# tutorial.net
KiCad netlist of a schematic drawn in EAGLE
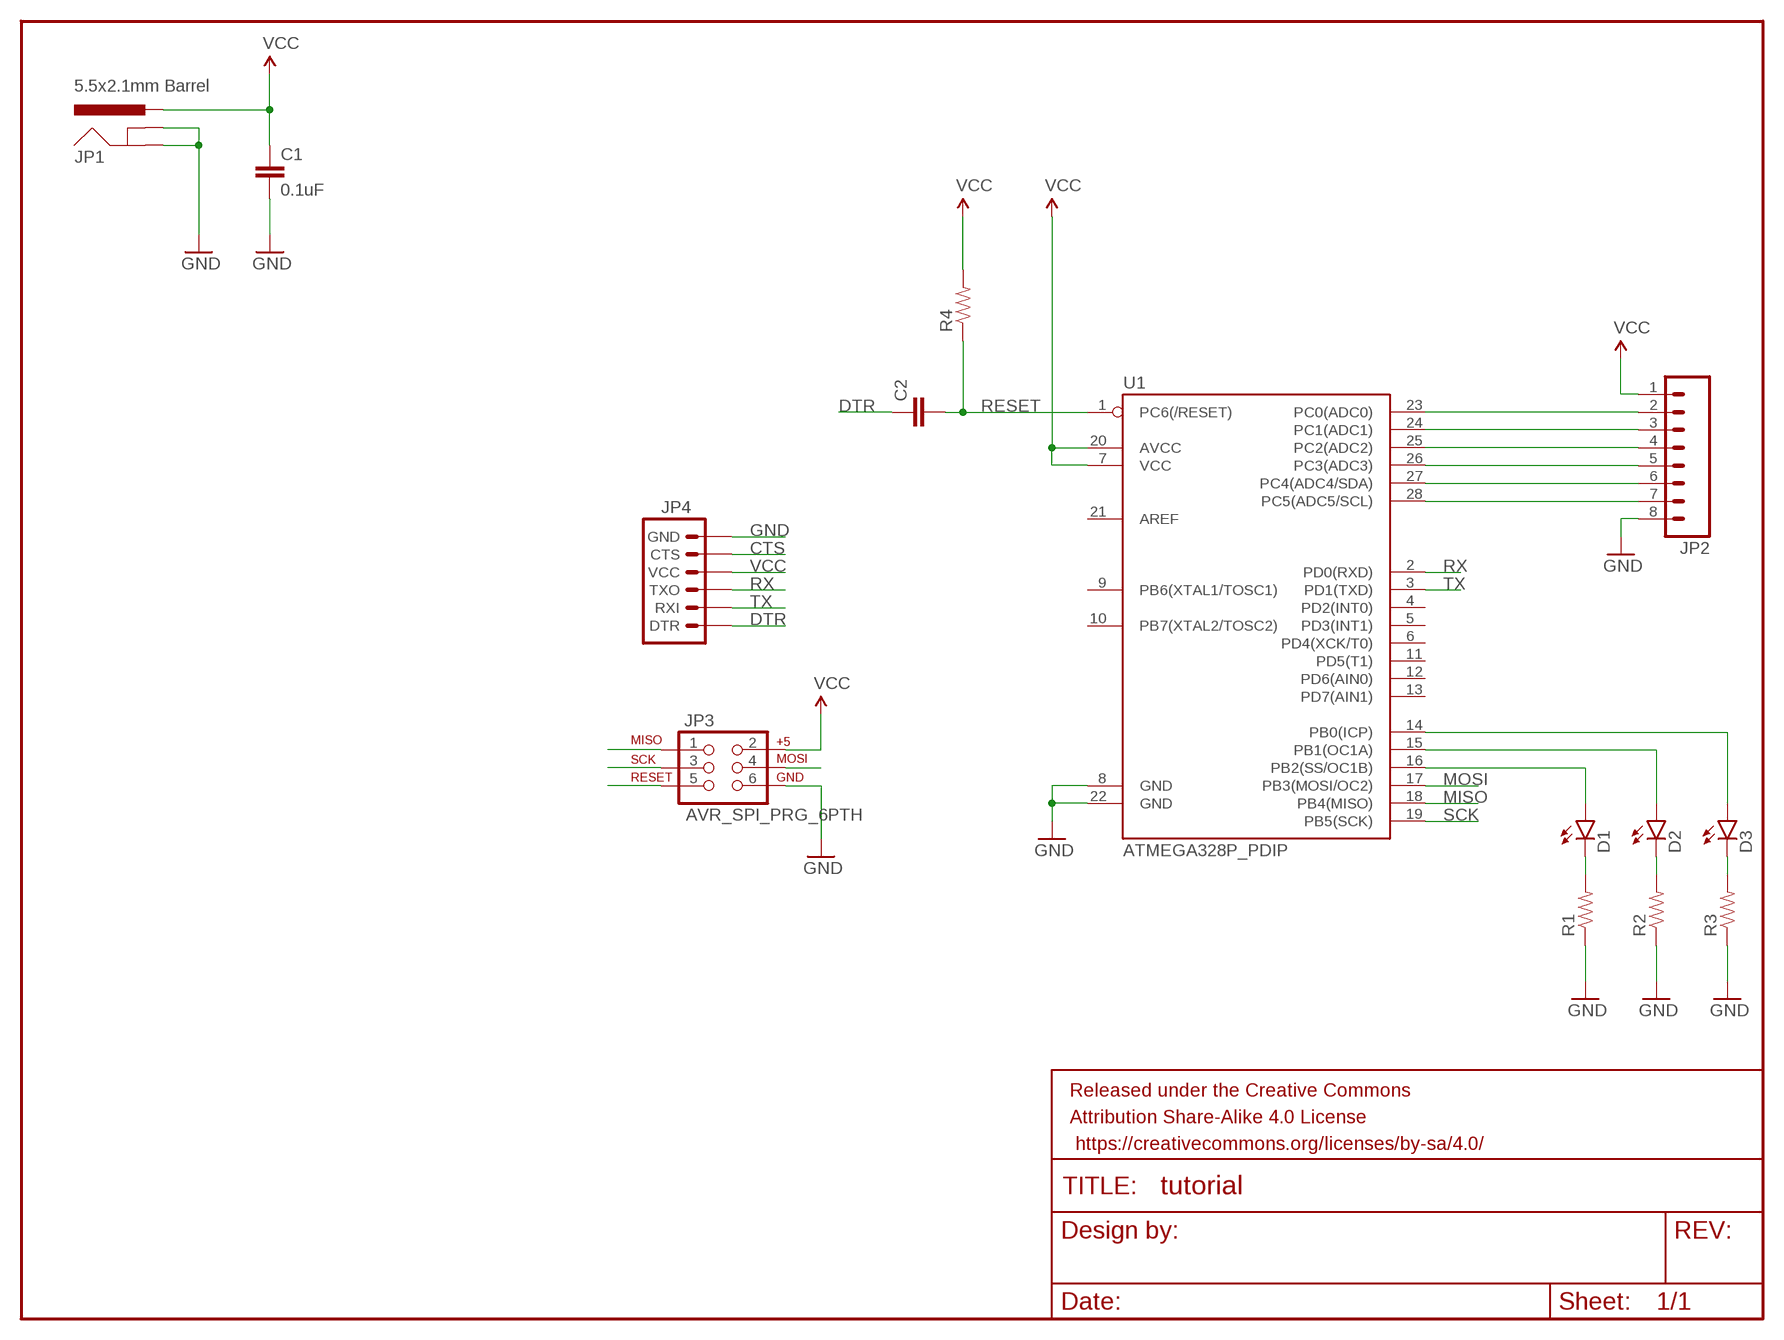
[diagram p0: schematic, sheet 1]

(export (version "E")
  (design (tool "Eeschema 10.0.6"))
  (components
    (comp (ref "C1")
      (value "0.1uF")
      (footprint "eagle-import:CAP-PTH-SMALL")
      (libsource (lib "eagle-import") (part "CAPPTH"))
    )
    (comp (ref "C2")
      (value "CAPPTH")
      (footprint "eagle-import:CAP-PTH-SMALL")
      (libsource (lib "eagle-import") (part "CAPPTH"))
    )
    (comp (ref "D1")
      (value "LED5MM")
      (footprint "eagle-import:LED5MM")
      (libsource (lib "eagle-import") (part "LED5MM"))
    )
    (comp (ref "D2")
      (value "LED5MM")
      (footprint "eagle-import:LED5MM")
      (libsource (lib "eagle-import") (part "LED5MM"))
    )
    (comp (ref "D3")
      (value "LED5MM")
      (footprint "eagle-import:LED5MM")
      (libsource (lib "eagle-import") (part "LED5MM"))
    )
    (comp (ref "FRAME1")
      (value "FRAME-LETTER")
      (footprint "eagle-import:CREATIVE_COMMONS")
      (libsource (lib "eagle-import") (part "FRAME-LETTER"))
    )
    (comp (ref "JP1")
      (value "5.5x2.1mm Barrel")
      (footprint "eagle-import:POWER_JACK_SMD")
      (libsource (lib "eagle-import") (part "POWER_JACKSMD"))
    )
    (comp (ref "JP2")
      (value "M08")
      (footprint "eagle-import:1X08_ROUND")
      (libsource (lib "eagle-import") (part "M08"))
    )
    (comp (ref "JP3")
      (value "AVR_SPI_PRG_6PTH")
      (footprint "eagle-import:2X3")
      (libsource (lib "eagle-import") (part "AVR_SPI_PRG_6PTH"))
    )
    (comp (ref "JP4")
      (value "ARDUINO_SERIAL_PROGRAMPTH")
      (footprint "eagle-import:1X06")
      (libsource (lib "eagle-import") (part "ARDUINO_SERIAL_PROGRAMPTH"))
    )
    (comp (ref "R1")
      (value "RESISTORPTH-1/4W")
      (footprint "eagle-import:AXIAL-0.4")
      (libsource (lib "eagle-import") (part "RESISTORPTH-1/4W"))
    )
    (comp (ref "R2")
      (value "RESISTORPTH-1/4W")
      (footprint "eagle-import:AXIAL-0.4")
      (libsource (lib "eagle-import") (part "RESISTORPTH-1/4W"))
    )
    (comp (ref "R3")
      (value "RESISTORPTH-1/4W")
      (footprint "eagle-import:AXIAL-0.4")
      (libsource (lib "eagle-import") (part "RESISTORPTH-1/4W"))
    )
    (comp (ref "R4")
      (value "RESISTORPTH-1/4W")
      (footprint "eagle-import:AXIAL-0.4")
      (libsource (lib "eagle-import") (part "RESISTORPTH-1/4W"))
    )
    (comp (ref "U1")
      (value "ATMEGA328P_PDIP")
      (footprint "eagle-import:DIL28-3")
      (libsource (lib "eagle-import") (part "ATMEGA328P_PDIP"))
    )
  )
  (nets
    (net (code "1") (name "/CTS") (class "Default")
      (node (ref "JP4") (pin "5") (pinfunction "CTS_5") (pintype "passive"))
    )
    (net (code "2") (name "/DTR") (class "Default")
      (node (ref "C2") (pin "1") (pinfunction "1_1") (pintype "passive"))
      (node (ref "JP4") (pin "1") (pinfunction "DTR_1") (pintype "passive"))
    )
    (net (code "3") (name "/MISO") (class "Default")
      (node (ref "JP3") (pin "1") (pinfunction "1_1") (pintype "passive"))
      (node (ref "U1") (pin "18") (pinfunction "PB4(MISO)_18") (pintype "bidirectional"))
    )
    (net (code "4") (name "/MOSI") (class "Default")
      (node (ref "JP3") (pin "4") (pinfunction "4_4") (pintype "passive"))
      (node (ref "U1") (pin "17") (pinfunction "PB3(MOSI/OC2)_17") (pintype "bidirectional"))
    )
    (net (code "5") (name "/RESET") (class "Default")
      (node (ref "C2") (pin "2") (pinfunction "2_2") (pintype "passive"))
      (node (ref "JP3") (pin "5") (pinfunction "5_5") (pintype "passive"))
      (node (ref "R4") (pin "P$1") (pinfunction "1_P$1") (pintype "passive"))
      (node (ref "U1") (pin "1") (pinfunction "PC6(/RESET)_1") (pintype "bidirectional"))
    )
    (net (code "6") (name "/RX") (class "Default")
      (node (ref "JP4") (pin "3") (pinfunction "TXO_3") (pintype "passive"))
      (node (ref "U1") (pin "2") (pinfunction "PD0(RXD)_2") (pintype "bidirectional"))
    )
    (net (code "7") (name "/SCK") (class "Default")
      (node (ref "JP3") (pin "3") (pinfunction "3_3") (pintype "passive"))
      (node (ref "U1") (pin "19") (pinfunction "PB5(SCK)_19") (pintype "bidirectional"))
    )
    (net (code "8") (name "/TX") (class "Default")
      (node (ref "JP4") (pin "2") (pinfunction "RXI_2") (pintype "passive"))
      (node (ref "U1") (pin "3") (pinfunction "PD1(TXD)_3") (pintype "bidirectional"))
    )
    (net (code "9") (name "GND") (class "Default")
      (node (ref "C1") (pin "2") (pinfunction "2_2") (pintype "passive"))
      (node (ref "JP1") (pin "GND") (pinfunction "GNDBREAK_GND") (pintype "bidirectional"))
      (node (ref "JP1") (pin "P$4") (pinfunction "GND_P$4") (pintype "bidirectional"))
      (node (ref "JP2") (pin "8") (pinfunction "8_8") (pintype "passive"))
      (node (ref "JP3") (pin "6") (pinfunction "6_6") (pintype "passive"))
      (node (ref "JP4") (pin "6") (pinfunction "GND_6") (pintype "passive"))
      (node (ref "R1") (pin "P$1") (pinfunction "1_P$1") (pintype "passive"))
      (node (ref "R2") (pin "P$1") (pinfunction "1_P$1") (pintype "passive"))
      (node (ref "R3") (pin "P$1") (pinfunction "1_P$1") (pintype "passive"))
      (node (ref "U1") (pin "22") (pinfunction "GND_22") (pintype "bidirectional"))
      (node (ref "U1") (pin "8") (pinfunction "GND_8") (pintype "bidirectional"))
    )
    (net (code "10") (name "Net-(D1-C)") (class "Default")
      (node (ref "D1") (pin "K") (pinfunction "C_K") (pintype "passive"))
      (node (ref "R1") (pin "P$2") (pinfunction "2_P$2") (pintype "passive"))
    )
    (net (code "11") (name "Net-(D2-C)") (class "Default")
      (node (ref "D2") (pin "K") (pinfunction "C_K") (pintype "passive"))
      (node (ref "R2") (pin "P$2") (pinfunction "2_P$2") (pintype "passive"))
    )
    (net (code "12") (name "Net-(D3-C)") (class "Default")
      (node (ref "D3") (pin "K") (pinfunction "C_K") (pintype "passive"))
      (node (ref "R3") (pin "P$2") (pinfunction "2_P$2") (pintype "passive"))
    )
    (net (code "13") (name "Net-(U1-PB0(ICP))") (class "Default")
      (node (ref "D3") (pin "A") (pinfunction "A_A") (pintype "passive"))
      (node (ref "U1") (pin "14") (pinfunction "PB0(ICP)_14") (pintype "bidirectional"))
    )
    (net (code "14") (name "Net-(U1-PB1(OC1A))") (class "Default")
      (node (ref "D2") (pin "A") (pinfunction "A_A") (pintype "passive"))
      (node (ref "U1") (pin "15") (pinfunction "PB1(OC1A)_15") (pintype "bidirectional"))
    )
    (net (code "15") (name "Net-(U1-PB2(SS{slash}OC1B))") (class "Default")
      (node (ref "D1") (pin "A") (pinfunction "A_A") (pintype "passive"))
      (node (ref "U1") (pin "16") (pinfunction "PB2(SS/OC1B)_16") (pintype "bidirectional"))
    )
    (net (code "16") (name "Net-(U1-PC0(ADC0))") (class "Default")
      (node (ref "JP2") (pin "2") (pinfunction "2_2") (pintype "passive"))
      (node (ref "U1") (pin "23") (pinfunction "PC0(ADC0)_23") (pintype "bidirectional"))
    )
    (net (code "17") (name "Net-(U1-PC1(ADC1))") (class "Default")
      (node (ref "JP2") (pin "3") (pinfunction "3_3") (pintype "passive"))
      (node (ref "U1") (pin "24") (pinfunction "PC1(ADC1)_24") (pintype "bidirectional"))
    )
    (net (code "18") (name "Net-(U1-PC2(ADC2))") (class "Default")
      (node (ref "JP2") (pin "4") (pinfunction "4_4") (pintype "passive"))
      (node (ref "U1") (pin "25") (pinfunction "PC2(ADC2)_25") (pintype "bidirectional"))
    )
    (net (code "19") (name "Net-(U1-PC3(ADC3))") (class "Default")
      (node (ref "JP2") (pin "5") (pinfunction "5_5") (pintype "passive"))
      (node (ref "U1") (pin "26") (pinfunction "PC3(ADC3)_26") (pintype "bidirectional"))
    )
    (net (code "20") (name "Net-(U1-PC4(ADC4{slash}SDA))") (class "Default")
      (node (ref "JP2") (pin "6") (pinfunction "6_6") (pintype "passive"))
      (node (ref "U1") (pin "27") (pinfunction "PC4(ADC4/SDA)_27") (pintype "bidirectional"))
    )
    (net (code "21") (name "Net-(U1-PC5(ADC5{slash}SCL))") (class "Default")
      (node (ref "JP2") (pin "7") (pinfunction "7_7") (pintype "passive"))
      (node (ref "U1") (pin "28") (pinfunction "PC5(ADC5/SCL)_28") (pintype "bidirectional"))
    )
    (net (code "22") (name "VCC") (class "Default")
      (node (ref "C1") (pin "1") (pinfunction "1_1") (pintype "passive"))
      (node (ref "JP1") (pin "VIN0") (pinfunction "PWR_VIN0") (pintype "bidirectional"))
      (node (ref "JP2") (pin "1") (pinfunction "1_1") (pintype "passive"))
      (node (ref "JP3") (pin "2") (pinfunction "2_2") (pintype "passive"))
      (node (ref "JP4") (pin "4") (pinfunction "VCC_4") (pintype "passive"))
      (node (ref "R4") (pin "P$2") (pinfunction "2_P$2") (pintype "passive"))
      (node (ref "U1") (pin "20") (pinfunction "AVCC_20") (pintype "bidirectional"))
      (node (ref "U1") (pin "7") (pinfunction "VCC_7") (pintype "bidirectional"))
    )
    (net (code "23") (name "unconnected-(U1-AREF-Pad21)") (class "Default")
      (node (ref "U1") (pin "21") (pinfunction "AREF_21") (pintype "bidirectional"))
    )
    (net (code "24") (name "unconnected-(U1-PB6(XTAL1{slash}TOSC1)-Pad9)") (class "Default")
      (node (ref "U1") (pin "9") (pinfunction "PB6(XTAL1/TOSC1)_9") (pintype "bidirectional"))
    )
    (net (code "25") (name "unconnected-(U1-PB7(XTAL2{slash}TOSC2)-Pad10)") (class "Default")
      (node (ref "U1") (pin "10") (pinfunction "PB7(XTAL2/TOSC2)_10") (pintype "bidirectional"))
    )
    (net (code "26") (name "unconnected-(U1-PD2(INT0)-Pad4)") (class "Default")
      (node (ref "U1") (pin "4") (pinfunction "PD2(INT0)_4") (pintype "bidirectional"))
    )
    (net (code "27") (name "unconnected-(U1-PD3(INT1)-Pad5)") (class "Default")
      (node (ref "U1") (pin "5") (pinfunction "PD3(INT1)_5") (pintype "bidirectional"))
    )
    (net (code "28") (name "unconnected-(U1-PD4(XCK{slash}T0)-Pad6)") (class "Default")
      (node (ref "U1") (pin "6") (pinfunction "PD4(XCK/T0)_6") (pintype "bidirectional"))
    )
    (net (code "29") (name "unconnected-(U1-PD5(T1)-Pad11)") (class "Default")
      (node (ref "U1") (pin "11") (pinfunction "PD5(T1)_11") (pintype "bidirectional"))
    )
    (net (code "30") (name "unconnected-(U1-PD6(AIN0)-Pad12)") (class "Default")
      (node (ref "U1") (pin "12") (pinfunction "PD6(AIN0)_12") (pintype "bidirectional"))
    )
    (net (code "31") (name "unconnected-(U1-PD7(AIN1)-Pad13)") (class "Default")
      (node (ref "U1") (pin "13") (pinfunction "PD7(AIN1)_13") (pintype "bidirectional"))
    )
  )
)
